# AltiumSTM32_Schematic.net
KiCad netlist of a schematic drawn in Altium Designer
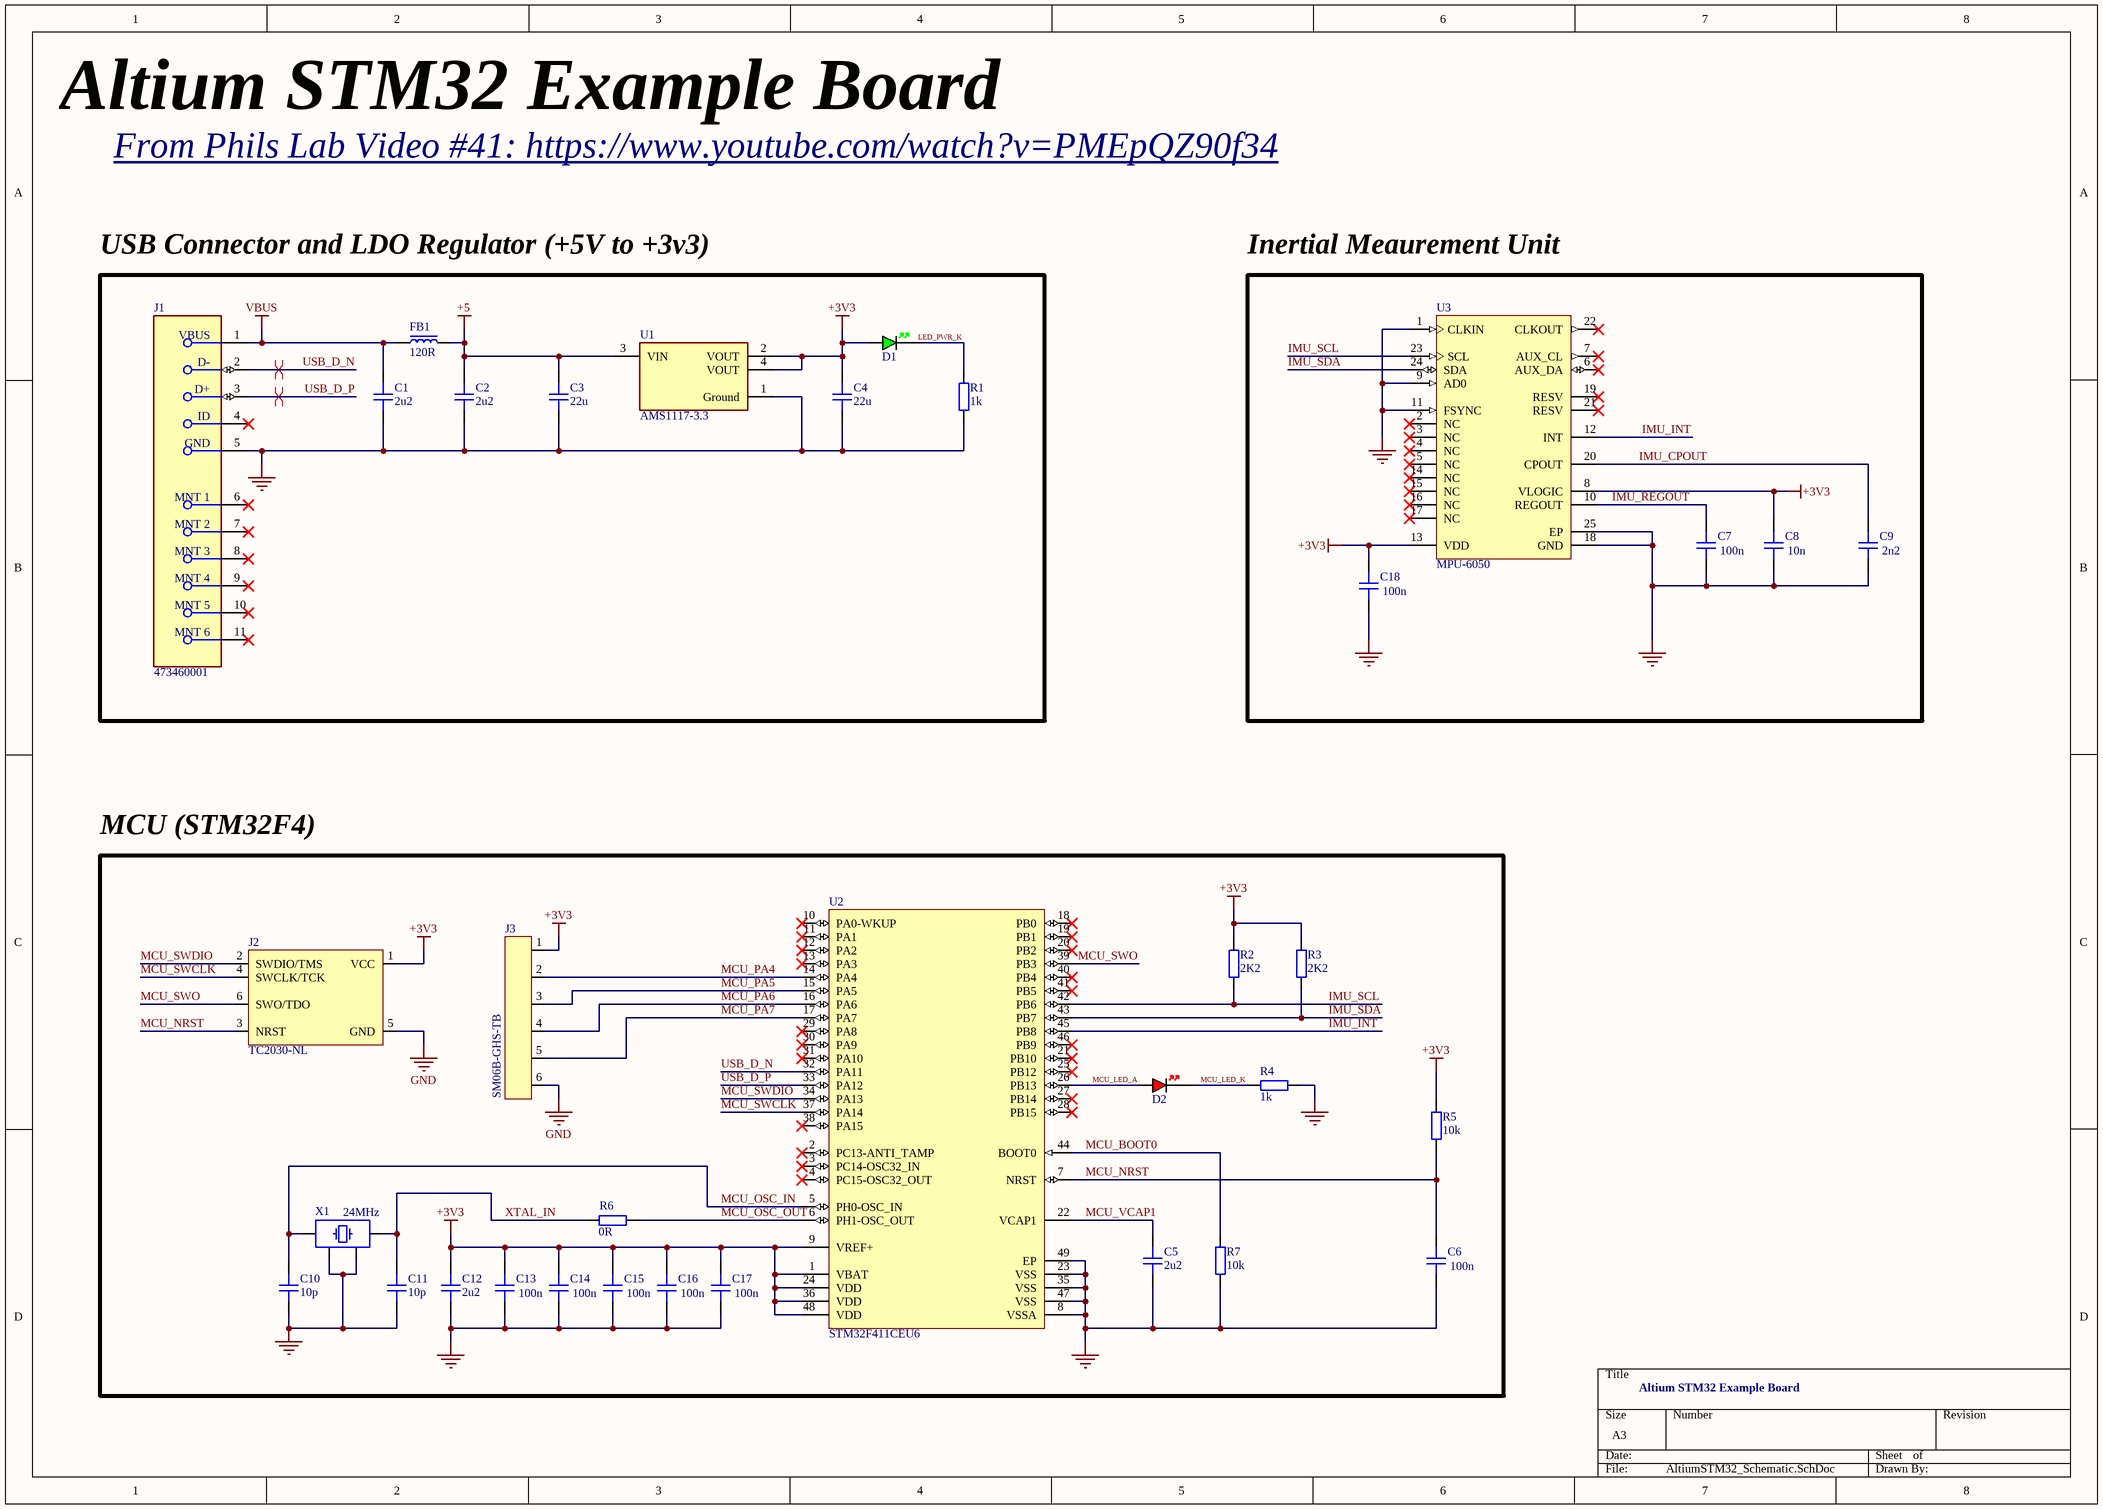
[diagram p0: AltiumSTM32_Schematic.SchDoc]

(export (version "E")
  (design (tool "Eeschema 10.0.6"))
  (components
    (comp (ref "C1")
      (value "2u2")
      (footprint "CAP_0603")
      (description "Capacitor SMD 0603")
      (libsource (lib "Schematic-Lib-PhilsLab") (part "CAP_0603"))
    )
    (comp (ref "C2")
      (value "2u2")
      (footprint "CAP_0603")
      (description "Capacitor SMD 0603")
      (libsource (lib "Schematic-Lib-PhilsLab") (part "CAP_0603"))
    )
    (comp (ref "C3")
      (value "22u")
      (footprint "CAP_0805")
      (description "Capacitor SMD 0805")
      (libsource (lib "Schematic-Lib-PhilsLab") (part "CAP_0805"))
    )
    (comp (ref "C4")
      (value "22u")
      (footprint "CAP_0805")
      (description "Capacitor SMD 0805")
      (libsource (lib "Schematic-Lib-PhilsLab") (part "CAP_0805"))
    )
    (comp (ref "C5")
      (value "2u2")
      (footprint "CAP_0603")
      (description "Capacitor SMD 0603")
      (libsource (lib "Schematic-Lib-PhilsLab") (part "CAP_0603"))
    )
    (comp (ref "C6")
      (value "100n")
      (footprint "CAP_0402")
      (description "Capacitor SMD 0402")
      (libsource (lib "Schematic-Lib-PhilsLab") (part "CAP_0402"))
    )
    (comp (ref "C7")
      (value "100n")
      (footprint "CAP_0402")
      (description "Capacitor SMD 0402")
      (libsource (lib "Schematic-Lib-PhilsLab") (part "CAP_0402"))
    )
    (comp (ref "C8")
      (value "10n")
      (footprint "CAP_0402")
      (description "Capacitor SMD 0402")
      (libsource (lib "Schematic-Lib-PhilsLab") (part "CAP_0402"))
    )
    (comp (ref "C9")
      (value "2n2")
      (footprint "CAP_0402")
      (description "Capacitor SMD 0402")
      (libsource (lib "Schematic-Lib-PhilsLab") (part "CAP_0402"))
    )
    (comp (ref "C10")
      (value "10p")
      (footprint "CAP_0402")
      (description "Capacitor SMD 0402")
      (libsource (lib "Schematic-Lib-PhilsLab") (part "CAP_0402"))
    )
    (comp (ref "C11")
      (value "10p")
      (footprint "CAP_0402")
      (description "Capacitor SMD 0402")
      (libsource (lib "Schematic-Lib-PhilsLab") (part "CAP_0402"))
    )
    (comp (ref "C12")
      (value "2u2")
      (footprint "CAP_0603")
      (description "Capacitor SMD 0603")
      (libsource (lib "Schematic-Lib-PhilsLab") (part "CAP_0603"))
    )
    (comp (ref "C13")
      (value "100n")
      (footprint "CAP_0402")
      (description "Capacitor SMD 0402")
      (libsource (lib "Schematic-Lib-PhilsLab") (part "CAP_0402"))
    )
    (comp (ref "C14")
      (value "100n")
      (footprint "CAP_0402")
      (description "Capacitor SMD 0402")
      (libsource (lib "Schematic-Lib-PhilsLab") (part "CAP_0402"))
    )
    (comp (ref "C15")
      (value "100n")
      (footprint "CAP_0402")
      (description "Capacitor SMD 0402")
      (libsource (lib "Schematic-Lib-PhilsLab") (part "CAP_0402"))
    )
    (comp (ref "C16")
      (value "100n")
      (footprint "CAP_0402")
      (description "Capacitor SMD 0402")
      (libsource (lib "Schematic-Lib-PhilsLab") (part "CAP_0402"))
    )
    (comp (ref "C17")
      (value "100n")
      (footprint "CAP_0402")
      (description "Capacitor SMD 0402")
      (libsource (lib "Schematic-Lib-PhilsLab") (part "CAP_0402"))
    )
    (comp (ref "C18")
      (value "100n")
      (footprint "CAP_0402")
      (description "Capacitor SMD 0402")
      (libsource (lib "Schematic-Lib-PhilsLab") (part "CAP_0402"))
    )
    (comp (ref "D1")
      (value "GREEN")
      (footprint "LED_0402_GREEN")
      (description "LED 0402 GREEN SMD")
      (libsource (lib "Schematic-Lib-PhilsLab") (part "LED_0402_GREEN"))
    )
    (comp (ref "D2")
      (value "RED")
      (footprint "LED_0402_RED")
      (description "LED 0402 RED SMD")
      (libsource (lib "Schematic-Lib-PhilsLab") (part "LED_0402_RED"))
    )
    (comp (ref "FB1")
      (value "120R")
      (footprint "FB_0603")
      (description "Ferrite Bead SMD 0603")
      (libsource (lib "Schematic-Lib-PhilsLab") (part "FB_0603"))
    )
    (comp (ref "J1")
      (value "473460001")
      (footprint "FP-473460001-MFG")
      (description "USB - micro B USB 2.0 Receptacle Connector 5 Position Surface Mount, Right Angle")
      (fields (field (name "OCTOPART") "https://octopart.com/47346-0001-molex-7164928"))
      (libsource (lib "Altium Content Vault") (part "53ae1f1d9b557310b43ca686e5bb76a"))
    )
    (comp (ref "J2")
      (value "TC2030-NL")
      (footprint "TC2030-NL-FP")
      (description "Tag-Connect No-Solder SWD Debug Connector (No Legs) DO NOT PLACE")
      (fields
        (field (name "MANUFACTURER") "Tag-Connect")
        (field (name "MANUFACTURER PART NUMBER") "TC2030-NL-FP")
      )
      (libsource (lib "Schematic-Lib-PhilsLab") (part "TC2030-NL"))
    )
    (comp (ref "J3")
      (value "SM06B-GHS-TB")
      (footprint "SM06B-GHS-TB")
      (description "Header Connector 6 Position 1.25MM Pitch SMD Horizontal JST GH")
      (fields (field (name "MANUFACTURER") "JST"))
      (libsource (lib "Schematic-Lib-PhilsLab") (part "SM06B-GHS-TB"))
    )
    (comp (ref "R1")
      (value "1k")
      (footprint "RES_0402")
      (description "Resistor SMD 0402")
      (libsource (lib "Schematic-Lib-PhilsLab") (part "RES_0402"))
    )
    (comp (ref "R2")
      (value "2K2")
      (footprint "RES_0402")
      (description "Resistor SMD 0402")
      (libsource (lib "Schematic-Lib-PhilsLab") (part "RES_0402"))
    )
    (comp (ref "R3")
      (value "2K2")
      (footprint "RES_0402")
      (description "Resistor SMD 0402")
      (libsource (lib "Schematic-Lib-PhilsLab") (part "RES_0402"))
    )
    (comp (ref "R4")
      (value "1k")
      (footprint "RES_0402")
      (description "Resistor SMD 0402")
      (libsource (lib "Schematic-Lib-PhilsLab") (part "RES_0402"))
    )
    (comp (ref "R5")
      (value "10k")
      (footprint "RES_0402")
      (description "Resistor SMD 0402")
      (libsource (lib "Schematic-Lib-PhilsLab") (part "RES_0402"))
    )
    (comp (ref "R6")
      (value "0R")
      (footprint "RES_0402")
      (description "Resistor SMD 0402")
      (libsource (lib "Schematic-Lib-PhilsLab") (part "RES_0402"))
    )
    (comp (ref "R7")
      (value "10k")
      (footprint "RES_0402")
      (description "Resistor SMD 0402")
      (libsource (lib "Schematic-Lib-PhilsLab") (part "RES_0402"))
    )
    (comp (ref "U1")
      (value "AMS1117-3.3")
      (footprint "FP-AMS1117-IPC_C")
      (description "LDO Voltage Regulators 1A, 3.3V")
      (fields
        (field (name "OCTOPART") "https://octopart.com/ams1117-3.3-advanced+monolithic+systems-25899300")
        (field (name "MANUFACTURER") "Advanced Monolithic Systems")
      )
      (libsource (lib "Altium Content Vault") (part "8bdbb5f8e77002000e30dd2845d0354"))
    )
    (comp (ref "U2")
      (value "STM32F411CEU6")
      (footprint "STM-UFQFPN48_L")
      (libsource (lib "Altium Content Vault") (part "MC-ARM-STM32F411-UFQFPN48"))
    )
    (comp (ref "U3")
      (value "MPU-6050")
      (footprint "IS-QFN-24_V")
      (fields (field (name "MANUFACTURER") "InvenSense"))
      (libsource (lib "Altium Content Vault") (part "IS-MPU-6050-QFN-24"))
    )
    (comp (ref "X1")
      (value "24MHz")
      (footprint "XTAL_3225")
      (description "Crystal SMD 24MHz 10PPM 7pF 3225")
      (fields
        (field (name "MANUFACTURER") "Epson")
        (field (name "MANUFACTURER PART NUMBER") "TSX-3225 24.0000MF15X-AC")
      )
      (libsource (lib "Schematic-Lib-PhilsLab") (part "TSX-3225_24.0000MF15X-AC"))
    )
  )
  (nets
    (net (code "1") (name "+3V3") (class "Default")
      (node (ref "C12") (pin "2") (pinfunction "2_2") (pintype "passive"))
      (node (ref "C13") (pin "2") (pinfunction "2_2") (pintype "passive"))
      (node (ref "C14") (pin "2") (pinfunction "2_2") (pintype "passive"))
      (node (ref "C15") (pin "2") (pinfunction "2_2") (pintype "passive"))
      (node (ref "C16") (pin "2") (pinfunction "2_2") (pintype "passive"))
      (node (ref "C17") (pin "2") (pinfunction "2_2") (pintype "passive"))
      (node (ref "C18") (pin "2") (pinfunction "2_2") (pintype "passive"))
      (node (ref "C4") (pin "2") (pinfunction "2_2") (pintype "passive"))
      (node (ref "C8") (pin "2") (pinfunction "2_2") (pintype "passive"))
      (node (ref "D1") (pin "A") (pinfunction "A_A") (pintype "passive"))
      (node (ref "J2") (pin "1") (pinfunction "VCC_1") (pintype "passive"))
      (node (ref "J3") (pin "1") (pinfunction "1_1") (pintype "passive"))
      (node (ref "R2") (pin "2") (pinfunction "2_2") (pintype "passive"))
      (node (ref "R3") (pin "2") (pinfunction "2_2") (pintype "passive"))
      (node (ref "R5") (pin "2") (pinfunction "2_2") (pintype "passive"))
      (node (ref "U1") (pin "2") (pinfunction "VOUT_2") (pintype "passive"))
      (node (ref "U1") (pin "4") (pinfunction "VOUT_4") (pintype "passive"))
      (node (ref "U2") (pin "1") (pinfunction "VBAT_1") (pintype "power_in"))
      (node (ref "U2") (pin "24") (pinfunction "VDD_24") (pintype "power_in"))
      (node (ref "U2") (pin "36") (pinfunction "VDD_36") (pintype "power_in"))
      (node (ref "U2") (pin "48") (pinfunction "VDD_48") (pintype "power_in"))
      (node (ref "U2") (pin "9") (pinfunction "VREF+_9") (pintype "power_in"))
      (node (ref "U3") (pin "13") (pinfunction "VDD_13") (pintype "power_in"))
      (node (ref "U3") (pin "8") (pinfunction "VLOGIC_8") (pintype "power_in"))
    )
    (net (code "2") (name "+5") (class "Default")
      (node (ref "C2") (pin "2") (pinfunction "2_2") (pintype "passive"))
      (node (ref "C3") (pin "2") (pinfunction "2_2") (pintype "passive"))
      (node (ref "FB1") (pin "2") (pinfunction "2_2") (pintype "passive"))
      (node (ref "U1") (pin "3") (pinfunction "VIN_3") (pintype "power_in"))
    )
    (net (code "3") (name "/IMU_CPOUT") (class "Default")
      (node (ref "C9") (pin "2") (pinfunction "2_2") (pintype "passive"))
      (node (ref "U3") (pin "20") (pinfunction "CPOUT_20") (pintype "passive"))
    )
    (net (code "4") (name "/IMU_INT") (class "Default")
      (node (ref "U2") (pin "45") (pinfunction "PB8_45") (pintype "bidirectional"))
      (node (ref "U3") (pin "12") (pinfunction "INT_12") (pintype "open_collector"))
    )
    (net (code "5") (name "/IMU_REGOUT") (class "Default")
      (node (ref "C7") (pin "2") (pinfunction "2_2") (pintype "passive"))
      (node (ref "U3") (pin "10") (pinfunction "REGOUT_10") (pintype "passive"))
    )
    (net (code "6") (name "/IMU_SCL") (class "Default")
      (node (ref "R2") (pin "1") (pinfunction "1_1") (pintype "passive"))
      (node (ref "U2") (pin "42") (pinfunction "PB6_42") (pintype "bidirectional"))
      (node (ref "U3") (pin "23") (pinfunction "SCL_23") (pintype "input"))
    )
    (net (code "7") (name "/IMU_SDA") (class "Default")
      (node (ref "R3") (pin "1") (pinfunction "1_1") (pintype "passive"))
      (node (ref "U2") (pin "43") (pinfunction "PB7_43") (pintype "bidirectional"))
      (node (ref "U3") (pin "24") (pinfunction "SDA_24") (pintype "bidirectional"))
    )
    (net (code "8") (name "/LED_PWR_K") (class "Default")
      (node (ref "D1") (pin "K") (pinfunction "K_K") (pintype "passive"))
      (node (ref "R1") (pin "2") (pinfunction "2_2") (pintype "passive"))
    )
    (net (code "9") (name "/MCU_BOOT0") (class "Default")
      (node (ref "R7") (pin "2") (pinfunction "2_2") (pintype "passive"))
      (node (ref "U2") (pin "44") (pinfunction "BOOT0_44") (pintype "input"))
    )
    (net (code "10") (name "/MCU_LED_A") (class "Default")
      (node (ref "D2") (pin "A") (pinfunction "A_A") (pintype "passive"))
      (node (ref "U2") (pin "26") (pinfunction "PB13_26") (pintype "bidirectional"))
    )
    (net (code "11") (name "/MCU_LED_K") (class "Default")
      (node (ref "D2") (pin "K") (pinfunction "K_K") (pintype "passive"))
      (node (ref "R4") (pin "2") (pinfunction "2_2") (pintype "passive"))
    )
    (net (code "12") (name "/MCU_NRST") (class "Default")
      (node (ref "C6") (pin "2") (pinfunction "2_2") (pintype "passive"))
      (node (ref "J2") (pin "3") (pinfunction "NRST_3") (pintype "passive"))
      (node (ref "R5") (pin "1") (pinfunction "1_1") (pintype "passive"))
      (node (ref "U2") (pin "7") (pinfunction "NRST_7") (pintype "bidirectional"))
    )
    (net (code "13") (name "/MCU_OSC_IN") (class "Default")
      (node (ref "C10") (pin "2") (pinfunction "2_2") (pintype "passive"))
      (node (ref "U2") (pin "5") (pinfunction "PH0-OSC_IN_5") (pintype "bidirectional"))
      (node (ref "X1") (pin "1") (pinfunction "1_1") (pintype "passive"))
    )
    (net (code "14") (name "/MCU_OSC_OUT") (class "Default")
      (node (ref "R6") (pin "2") (pinfunction "2_2") (pintype "passive"))
      (node (ref "U2") (pin "6") (pinfunction "PH1-OSC_OUT_6") (pintype "bidirectional"))
    )
    (net (code "15") (name "/MCU_PA4") (class "Default")
      (node (ref "J3") (pin "2") (pinfunction "2_2") (pintype "passive"))
      (node (ref "U2") (pin "14") (pinfunction "PA4_14") (pintype "bidirectional"))
    )
    (net (code "16") (name "/MCU_PA5") (class "Default")
      (node (ref "J3") (pin "3") (pinfunction "3_3") (pintype "passive"))
      (node (ref "U2") (pin "15") (pinfunction "PA5_15") (pintype "bidirectional"))
    )
    (net (code "17") (name "/MCU_PA6") (class "Default")
      (node (ref "J3") (pin "4") (pinfunction "4_4") (pintype "passive"))
      (node (ref "U2") (pin "16") (pinfunction "PA6_16") (pintype "bidirectional"))
    )
    (net (code "18") (name "/MCU_PA7") (class "Default")
      (node (ref "J3") (pin "5") (pinfunction "5_5") (pintype "passive"))
      (node (ref "U2") (pin "17") (pinfunction "PA7_17") (pintype "bidirectional"))
    )
    (net (code "19") (name "/MCU_SWCLK") (class "Default")
      (node (ref "J2") (pin "4") (pinfunction "SWCLK/TCK_4") (pintype "passive"))
      (node (ref "U2") (pin "37") (pinfunction "PA14_37") (pintype "bidirectional"))
    )
    (net (code "20") (name "/MCU_SWDIO") (class "Default")
      (node (ref "J2") (pin "2") (pinfunction "SWDIO/TMS_2") (pintype "passive"))
      (node (ref "U2") (pin "34") (pinfunction "PA13_34") (pintype "bidirectional"))
    )
    (net (code "21") (name "/MCU_SWO") (class "Default")
      (node (ref "J2") (pin "6") (pinfunction "SWO/TDO_6") (pintype "passive"))
      (node (ref "U2") (pin "39") (pinfunction "PB3_39") (pintype "bidirectional"))
    )
    (net (code "22") (name "/MCU_VCAP1") (class "Default")
      (node (ref "C5") (pin "2") (pinfunction "2_2") (pintype "passive"))
      (node (ref "U2") (pin "22") (pinfunction "VCAP1_22") (pintype "passive"))
    )
    (net (code "23") (name "/USB_D_N") (class "Default")
      (node (ref "J1") (pin "2") (pinfunction "D-_2") (pintype "bidirectional"))
      (node (ref "U2") (pin "32") (pinfunction "PA11_32") (pintype "bidirectional"))
    )
    (net (code "24") (name "/USB_D_P") (class "Default")
      (node (ref "J1") (pin "3") (pinfunction "D+_3") (pintype "bidirectional"))
      (node (ref "U2") (pin "33") (pinfunction "PA12_33") (pintype "bidirectional"))
    )
    (net (code "25") (name "/XTAL_IN") (class "Default")
      (node (ref "C11") (pin "2") (pinfunction "2_2") (pintype "passive"))
      (node (ref "R6") (pin "1") (pinfunction "1_1") (pintype "passive"))
      (node (ref "X1") (pin "3") (pinfunction "3_3") (pintype "passive"))
    )
    (net (code "26") (name "GND") (class "Default")
      (node (ref "C1") (pin "1") (pinfunction "1_1") (pintype "passive"))
      (node (ref "C10") (pin "1") (pinfunction "1_1") (pintype "passive"))
      (node (ref "C11") (pin "1") (pinfunction "1_1") (pintype "passive"))
      (node (ref "C12") (pin "1") (pinfunction "1_1") (pintype "passive"))
      (node (ref "C13") (pin "1") (pinfunction "1_1") (pintype "passive"))
      (node (ref "C14") (pin "1") (pinfunction "1_1") (pintype "passive"))
      (node (ref "C15") (pin "1") (pinfunction "1_1") (pintype "passive"))
      (node (ref "C16") (pin "1") (pinfunction "1_1") (pintype "passive"))
      (node (ref "C17") (pin "1") (pinfunction "1_1") (pintype "passive"))
      (node (ref "C18") (pin "1") (pinfunction "1_1") (pintype "passive"))
      (node (ref "C2") (pin "1") (pinfunction "1_1") (pintype "passive"))
      (node (ref "C3") (pin "1") (pinfunction "1_1") (pintype "passive"))
      (node (ref "C4") (pin "1") (pinfunction "1_1") (pintype "passive"))
      (node (ref "C5") (pin "1") (pinfunction "1_1") (pintype "passive"))
      (node (ref "C6") (pin "1") (pinfunction "1_1") (pintype "passive"))
      (node (ref "C7") (pin "1") (pinfunction "1_1") (pintype "passive"))
      (node (ref "C8") (pin "1") (pinfunction "1_1") (pintype "passive"))
      (node (ref "C9") (pin "1") (pinfunction "1_1") (pintype "passive"))
      (node (ref "J1") (pin "5") (pinfunction "GND_5") (pintype "power_in"))
      (node (ref "J2") (pin "5") (pinfunction "GND_5") (pintype "passive"))
      (node (ref "J3") (pin "6") (pinfunction "6_6") (pintype "passive"))
      (node (ref "R1") (pin "1") (pinfunction "1_1") (pintype "passive"))
      (node (ref "R4") (pin "1") (pinfunction "1_1") (pintype "passive"))
      (node (ref "R7") (pin "1") (pinfunction "1_1") (pintype "passive"))
      (node (ref "U1") (pin "1") (pinfunction "Ground_1") (pintype "power_in"))
      (node (ref "U2") (pin "23") (pinfunction "VSS_23") (pintype "power_in"))
      (node (ref "U2") (pin "35") (pinfunction "VSS_35") (pintype "power_in"))
      (node (ref "U2") (pin "47") (pinfunction "VSS_47") (pintype "power_in"))
      (node (ref "U2") (pin "49") (pinfunction "EP_49") (pintype "power_in"))
      (node (ref "U2") (pin "8") (pinfunction "VSSA_8") (pintype "power_in"))
      (node (ref "U3") (pin "1") (pinfunction "CLKIN_1") (pintype "input"))
      (node (ref "U3") (pin "11") (pinfunction "FSYNC_11") (pintype "input"))
      (node (ref "U3") (pin "18") (pinfunction "GND_18") (pintype "power_in"))
      (node (ref "U3") (pin "25") (pinfunction "EP_25") (pintype "power_in"))
      (node (ref "U3") (pin "9") (pinfunction "AD0_9") (pintype "input"))
      (node (ref "X1") (pin "2") (pinfunction "2_2") (pintype "passive"))
      (node (ref "X1") (pin "4") (pinfunction "4_4") (pintype "passive"))
    )
    (net (code "27") (name "VBUS") (class "Default")
      (node (ref "C1") (pin "2") (pinfunction "2_2") (pintype "passive"))
      (node (ref "FB1") (pin "1") (pinfunction "1_1") (pintype "passive"))
      (node (ref "J1") (pin "1") (pinfunction "VBUS_1") (pintype "power_in"))
    )
    (net (code "28") (name "unconnected-(J1-ID-Pad4)") (class "Default")
      (node (ref "J1") (pin "4") (pinfunction "ID_4") (pintype "passive+no_connect"))
    )
    (net (code "29") (name "unconnected-(J1-MNT_1-Pad6)") (class "Default")
      (node (ref "J1") (pin "6") (pinfunction "MNT_1_6") (pintype "passive+no_connect"))
    )
    (net (code "30") (name "unconnected-(J1-MNT_2-Pad7)") (class "Default")
      (node (ref "J1") (pin "7") (pinfunction "MNT_2_7") (pintype "passive+no_connect"))
    )
    (net (code "31") (name "unconnected-(J1-MNT_3-Pad8)") (class "Default")
      (node (ref "J1") (pin "8") (pinfunction "MNT_3_8") (pintype "passive+no_connect"))
    )
    (net (code "32") (name "unconnected-(J1-MNT_4-Pad9)") (class "Default")
      (node (ref "J1") (pin "9") (pinfunction "MNT_4_9") (pintype "passive+no_connect"))
    )
    (net (code "33") (name "unconnected-(J1-MNT_5-Pad10)") (class "Default")
      (node (ref "J1") (pin "10") (pinfunction "MNT_5_10") (pintype "passive+no_connect"))
    )
    (net (code "34") (name "unconnected-(J1-MNT_6-Pad11)") (class "Default")
      (node (ref "J1") (pin "11") (pinfunction "MNT_6_11") (pintype "passive+no_connect"))
    )
    (net (code "35") (name "unconnected-(U2-PA0-WKUP-Pad10)") (class "Default")
      (node (ref "U2") (pin "10") (pinfunction "PA0-WKUP_10") (pintype "bidirectional+no_connect"))
    )
    (net (code "36") (name "unconnected-(U2-PA1-Pad11)") (class "Default")
      (node (ref "U2") (pin "11") (pinfunction "PA1_11") (pintype "bidirectional+no_connect"))
    )
    (net (code "37") (name "unconnected-(U2-PA2-Pad12)") (class "Default")
      (node (ref "U2") (pin "12") (pinfunction "PA2_12") (pintype "bidirectional+no_connect"))
    )
    (net (code "38") (name "unconnected-(U2-PA3-Pad13)") (class "Default")
      (node (ref "U2") (pin "13") (pinfunction "PA3_13") (pintype "bidirectional+no_connect"))
    )
    (net (code "39") (name "unconnected-(U2-PA8-Pad29)") (class "Default")
      (node (ref "U2") (pin "29") (pinfunction "PA8_29") (pintype "bidirectional+no_connect"))
    )
    (net (code "40") (name "unconnected-(U2-PA9-Pad30)") (class "Default")
      (node (ref "U2") (pin "30") (pinfunction "PA9_30") (pintype "bidirectional+no_connect"))
    )
    (net (code "41") (name "unconnected-(U2-PA10-Pad31)") (class "Default")
      (node (ref "U2") (pin "31") (pinfunction "PA10_31") (pintype "bidirectional+no_connect"))
    )
    (net (code "42") (name "unconnected-(U2-PA15-Pad38)") (class "Default")
      (node (ref "U2") (pin "38") (pinfunction "PA15_38") (pintype "bidirectional+no_connect"))
    )
    (net (code "43") (name "unconnected-(U2-PB0-Pad18)") (class "Default")
      (node (ref "U2") (pin "18") (pinfunction "PB0_18") (pintype "bidirectional+no_connect"))
    )
    (net (code "44") (name "unconnected-(U2-PB1-Pad19)") (class "Default")
      (node (ref "U2") (pin "19") (pinfunction "PB1_19") (pintype "bidirectional+no_connect"))
    )
    (net (code "45") (name "unconnected-(U2-PB2-Pad20)") (class "Default")
      (node (ref "U2") (pin "20") (pinfunction "PB2_20") (pintype "bidirectional+no_connect"))
    )
    (net (code "46") (name "unconnected-(U2-PB4-Pad40)") (class "Default")
      (node (ref "U2") (pin "40") (pinfunction "PB4_40") (pintype "bidirectional+no_connect"))
    )
    (net (code "47") (name "unconnected-(U2-PB5-Pad41)") (class "Default")
      (node (ref "U2") (pin "41") (pinfunction "PB5_41") (pintype "bidirectional+no_connect"))
    )
    (net (code "48") (name "unconnected-(U2-PB9-Pad46)") (class "Default")
      (node (ref "U2") (pin "46") (pinfunction "PB9_46") (pintype "bidirectional+no_connect"))
    )
    (net (code "49") (name "unconnected-(U2-PB10-Pad21)") (class "Default")
      (node (ref "U2") (pin "21") (pinfunction "PB10_21") (pintype "bidirectional+no_connect"))
    )
    (net (code "50") (name "unconnected-(U2-PB12-Pad25)") (class "Default")
      (node (ref "U2") (pin "25") (pinfunction "PB12_25") (pintype "bidirectional+no_connect"))
    )
    (net (code "51") (name "unconnected-(U2-PB14-Pad27)") (class "Default")
      (node (ref "U2") (pin "27") (pinfunction "PB14_27") (pintype "bidirectional+no_connect"))
    )
    (net (code "52") (name "unconnected-(U2-PB15-Pad28)") (class "Default")
      (node (ref "U2") (pin "28") (pinfunction "PB15_28") (pintype "bidirectional+no_connect"))
    )
    (net (code "53") (name "unconnected-(U2-PC13-ANTI_TAMP-Pad2)") (class "Default")
      (node (ref "U2") (pin "2") (pinfunction "PC13-ANTI_TAMP_2") (pintype "bidirectional+no_connect"))
    )
    (net (code "54") (name "unconnected-(U2-PC14-OSC32_IN-Pad3)") (class "Default")
      (node (ref "U2") (pin "3") (pinfunction "PC14-OSC32_IN_3") (pintype "bidirectional+no_connect"))
    )
    (net (code "55") (name "unconnected-(U2-PC15-OSC32_OUT-Pad4)") (class "Default")
      (node (ref "U2") (pin "4") (pinfunction "PC15-OSC32_OUT_4") (pintype "bidirectional+no_connect"))
    )
    (net (code "56") (name "unconnected-(U3-AUX_CL-Pad7)") (class "Default")
      (node (ref "U3") (pin "7") (pinfunction "AUX_CL_7") (pintype "output+no_connect"))
    )
    (net (code "57") (name "unconnected-(U3-AUX_DA-Pad6)") (class "Default")
      (node (ref "U3") (pin "6") (pinfunction "AUX_DA_6") (pintype "bidirectional+no_connect"))
    )
    (net (code "58") (name "unconnected-(U3-CLKOUT-Pad22)") (class "Default")
      (node (ref "U3") (pin "22") (pinfunction "CLKOUT_22") (pintype "output+no_connect"))
    )
    (net (code "59") (name "unconnected-(U3-NC-Pad2)") (class "Default")
      (node (ref "U3") (pin "2") (pinfunction "NC_2") (pintype "passive+no_connect"))
    )
    (net (code "60") (name "unconnected-(U3-NC-Pad3)") (class "Default")
      (node (ref "U3") (pin "3") (pinfunction "NC_3") (pintype "passive+no_connect"))
    )
    (net (code "61") (name "unconnected-(U3-NC-Pad4)") (class "Default")
      (node (ref "U3") (pin "4") (pinfunction "NC_4") (pintype "passive+no_connect"))
    )
    (net (code "62") (name "unconnected-(U3-NC-Pad5)") (class "Default")
      (node (ref "U3") (pin "5") (pinfunction "NC_5") (pintype "passive+no_connect"))
    )
    (net (code "63") (name "unconnected-(U3-NC-Pad14)") (class "Default")
      (node (ref "U3") (pin "14") (pinfunction "NC_14") (pintype "passive+no_connect"))
    )
    (net (code "64") (name "unconnected-(U3-NC-Pad15)") (class "Default")
      (node (ref "U3") (pin "15") (pinfunction "NC_15") (pintype "passive+no_connect"))
    )
    (net (code "65") (name "unconnected-(U3-NC-Pad16)") (class "Default")
      (node (ref "U3") (pin "16") (pinfunction "NC_16") (pintype "passive+no_connect"))
    )
    (net (code "66") (name "unconnected-(U3-NC-Pad17)") (class "Default")
      (node (ref "U3") (pin "17") (pinfunction "NC_17") (pintype "passive+no_connect"))
    )
    (net (code "67") (name "unconnected-(U3-RESV-Pad19)") (class "Default")
      (node (ref "U3") (pin "19") (pinfunction "RESV_19") (pintype "passive+no_connect"))
    )
    (net (code "68") (name "unconnected-(U3-RESV-Pad21)") (class "Default")
      (node (ref "U3") (pin "21") (pinfunction "RESV_21") (pintype "passive+no_connect"))
    )
  )
)
